# IndoorStation_PCB_M3.net
KiCad netlist of a schematic drawn in EAGLE
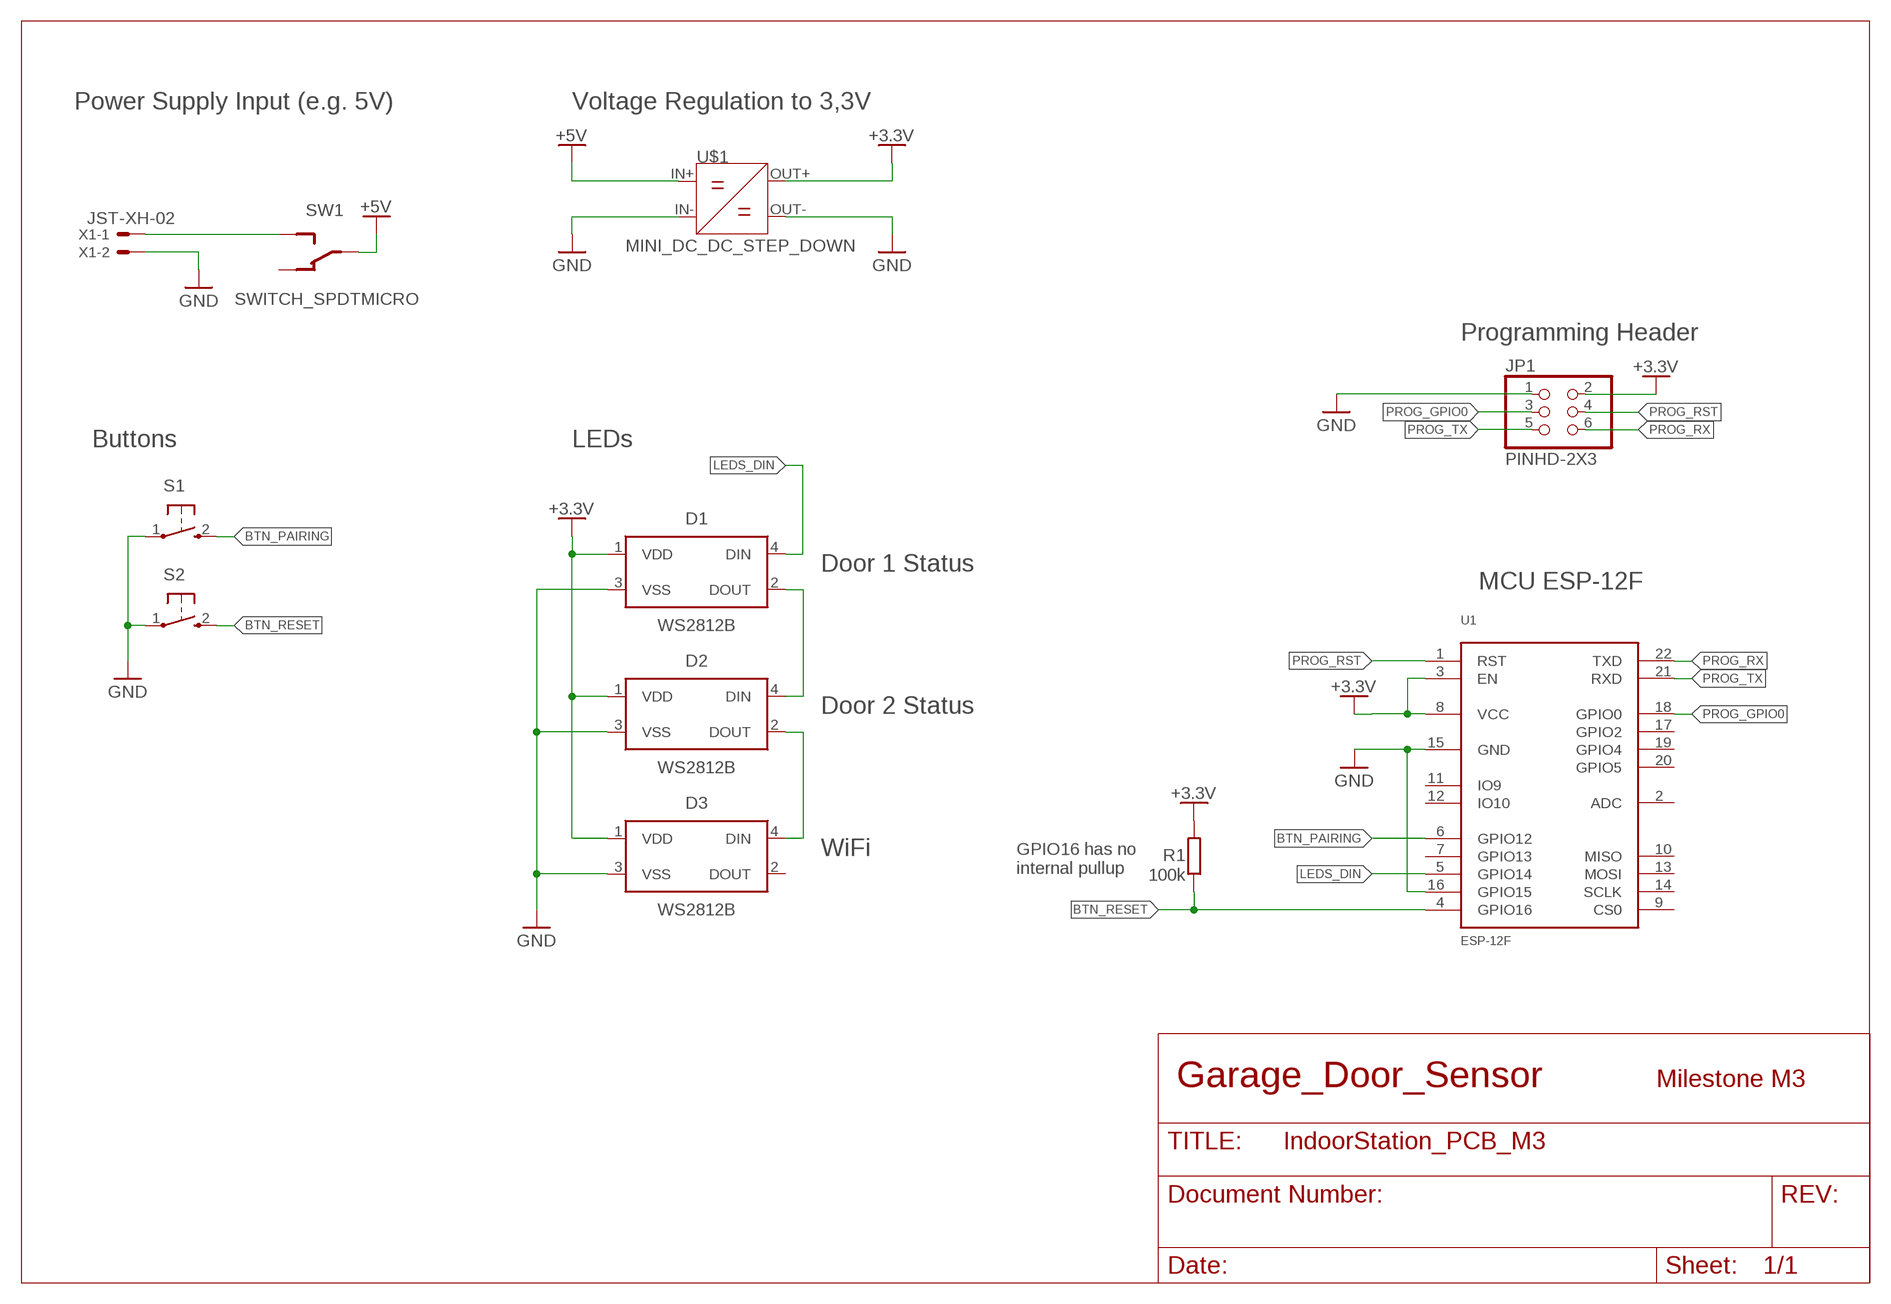
[diagram p0: schematic, sheet 1]

(export (version "E")
  (design (tool "Eeschema 10.0.6"))
  (components
    (comp (ref "D1")
      (value "WS2812B")
      (footprint "eagle-import:WS2812B")
      (fields (field (name "MANUFACTURER") "Worldsemi"))
      (libsource (lib "eagle-import") (part "WS2812B"))
    )
    (comp (ref "D2")
      (value "WS2812B")
      (footprint "eagle-import:WS2812B")
      (fields (field (name "MANUFACTURER") "Worldsemi"))
      (libsource (lib "eagle-import") (part "WS2812B"))
    )
    (comp (ref "D3")
      (value "WS2812B")
      (footprint "eagle-import:WS2812B")
      (fields (field (name "MANUFACTURER") "Worldsemi"))
      (libsource (lib "eagle-import") (part "WS2812B"))
    )
    (comp (ref "JP1")
      (value "PINHD-2X3")
      (footprint "eagle-import:2X03")
      (fields (field (name "MANUFACTURER") "Generic"))
      (libsource (lib "eagle-import") (part "PINHD-2X3"))
    )
    (comp (ref "R1")
      (value "100k")
      (footprint "eagle-import:R0805")
      (libsource (lib "eagle-import") (part "R-EU_R0805"))
    )
    (comp (ref "S1")
      (value "KURZHUBTASTER")
      (footprint "eagle-import:B3F-10XX")
      (libsource (lib "eagle-import") (part "KURZHUBTASTER"))
    )
    (comp (ref "S2")
      (value "KURZHUBTASTER")
      (footprint "eagle-import:B3F-10XX")
      (libsource (lib "eagle-import") (part "KURZHUBTASTER"))
    )
    (comp (ref "SW1")
      (value "SWITCH_SPDTMICRO")
      (footprint "eagle-import:MICROSWITCH_SPDT")
      (libsource (lib "eagle-import") (part "SWITCH_SPDTMICRO"))
    )
    (comp (ref "U$1")
      (value "MINI_DC_DC_STEP_DOWN")
      (footprint "eagle-import:MINI_DC_DC_STEP_DOWN")
      (libsource (lib "eagle-import") (part "MINI_DC_DC_STEP_DOWN"))
    )
    (comp (ref "U1")
      (value "ESP-12F")
      (footprint "eagle-import:ESP-12F")
      (fields (field (name "MF") "AI-Thinker"))
      (libsource (lib "eagle-import") (part "ESP-12F"))
    )
    (comp (ref "X1")
      (value "JST-XH-02")
      (footprint "eagle-import:JST-XH-02-EDGE")
      (libsource (lib "eagle-import") (part "JST-XH-02-PIN-EDGE"))
    )
  )
  (nets
    (net (code "1") (name "+3.3V") (class "Default")
      (node (ref "D1") (pin "1") (pinfunction "VDD_1") (pintype "power_in"))
      (node (ref "D2") (pin "1") (pinfunction "VDD_1") (pintype "power_in"))
      (node (ref "D3") (pin "1") (pinfunction "VDD_1") (pintype "power_in"))
      (node (ref "JP1") (pin "2") (pinfunction "2_2") (pintype "passive"))
      (node (ref "R1") (pin "2") (pinfunction "2_2") (pintype "passive"))
      (node (ref "U$1") (pin "OUT+") (pinfunction "OUT+_OUT+") (pintype "output"))
      (node (ref "U1") (pin "3") (pinfunction "EN_3") (pintype "bidirectional"))
      (node (ref "U1") (pin "8") (pinfunction "VCC_8") (pintype "bidirectional"))
    )
    (net (code "2") (name "+5V") (class "Default")
      (node (ref "SW1") (pin "P$2") (pinfunction "P$2_P$2") (pintype "passive"))
      (node (ref "U$1") (pin "IN+") (pinfunction "IN+_IN+") (pintype "input"))
    )
    (net (code "3") (name "BTN_PAIRING") (class "Default")
      (node (ref "S1") (pin "2") (pinfunction "S_2") (pintype "passive"))
      (node (ref "U1") (pin "6") (pinfunction "GPIO12_6") (pintype "bidirectional"))
    )
    (net (code "4") (name "BTN_RESET") (class "Default")
      (node (ref "R1") (pin "1") (pinfunction "1_1") (pintype "passive"))
      (node (ref "S2") (pin "2") (pinfunction "S_2") (pintype "passive"))
      (node (ref "U1") (pin "4") (pinfunction "GPIO16_4") (pintype "bidirectional"))
    )
    (net (code "5") (name "GND") (class "Default")
      (node (ref "D1") (pin "3") (pinfunction "VSS_3") (pintype "power_in"))
      (node (ref "D2") (pin "3") (pinfunction "VSS_3") (pintype "power_in"))
      (node (ref "D3") (pin "3") (pinfunction "VSS_3") (pintype "power_in"))
      (node (ref "JP1") (pin "1") (pinfunction "1_1") (pintype "passive"))
      (node (ref "S1") (pin "1") (pinfunction "P_1") (pintype "passive"))
      (node (ref "S2") (pin "1") (pinfunction "P_1") (pintype "passive"))
      (node (ref "U$1") (pin "IN-") (pinfunction "IN-_IN-") (pintype "input"))
      (node (ref "U$1") (pin "OUT-") (pinfunction "OUT-_OUT-") (pintype "output"))
      (node (ref "U1") (pin "15") (pinfunction "GND_15") (pintype "bidirectional"))
      (node (ref "U1") (pin "16") (pinfunction "GPIO15_16") (pintype "bidirectional"))
      (node (ref "X1") (pin "P$2") (pinfunction "S_P$2") (pintype "passive"))
    )
    (net (code "6") (name "LEDS_DIN") (class "Default")
      (node (ref "D1") (pin "4") (pinfunction "DIN_4") (pintype "input"))
      (node (ref "U1") (pin "5") (pinfunction "GPIO14_5") (pintype "bidirectional"))
    )
    (net (code "7") (name "Net-(D1-DOUT)") (class "Default")
      (node (ref "D1") (pin "2") (pinfunction "DOUT_2") (pintype "output"))
      (node (ref "D2") (pin "4") (pinfunction "DIN_4") (pintype "input"))
    )
    (net (code "8") (name "Net-(D2-DOUT)") (class "Default")
      (node (ref "D2") (pin "2") (pinfunction "DOUT_2") (pintype "output"))
      (node (ref "D3") (pin "4") (pinfunction "DIN_4") (pintype "input"))
    )
    (net (code "9") (name "Net-(X1A-S)") (class "Default")
      (node (ref "SW1") (pin "P$1") (pinfunction "P$1_P$1") (pintype "passive"))
      (node (ref "X1") (pin "P$1") (pinfunction "S_P$1") (pintype "passive"))
    )
    (net (code "10") (name "PROG_GPIO0") (class "Default")
      (node (ref "JP1") (pin "3") (pinfunction "3_3") (pintype "passive"))
      (node (ref "U1") (pin "18") (pinfunction "GPIO0_18") (pintype "bidirectional"))
    )
    (net (code "11") (name "PROG_RST") (class "Default")
      (node (ref "JP1") (pin "4") (pinfunction "4_4") (pintype "passive"))
      (node (ref "U1") (pin "1") (pinfunction "RST_1") (pintype "bidirectional"))
    )
    (net (code "12") (name "PROG_RX") (class "Default")
      (node (ref "JP1") (pin "6") (pinfunction "6_6") (pintype "passive"))
      (node (ref "U1") (pin "22") (pinfunction "TXD_22") (pintype "bidirectional"))
    )
    (net (code "13") (name "PROG_TX") (class "Default")
      (node (ref "JP1") (pin "5") (pinfunction "5_5") (pintype "passive"))
      (node (ref "U1") (pin "21") (pinfunction "RXD_21") (pintype "bidirectional"))
    )
    (net (code "14") (name "unconnected-(D3-DOUT-Pad2)") (class "Default")
      (node (ref "D3") (pin "2") (pinfunction "DOUT_2") (pintype "output"))
    )
    (net (code "15") (name "unconnected-(SW1-PadP$3)") (class "Default")
      (node (ref "SW1") (pin "P$3") (pinfunction "P$3_P$3") (pintype "passive"))
    )
    (net (code "16") (name "unconnected-(U1-ADC-Pad2)") (class "Default")
      (node (ref "U1") (pin "2") (pinfunction "ADC_2") (pintype "bidirectional"))
    )
    (net (code "17") (name "unconnected-(U1-CS0-Pad9)") (class "Default")
      (node (ref "U1") (pin "9") (pinfunction "CS0_9") (pintype "bidirectional"))
    )
    (net (code "18") (name "unconnected-(U1-GPIO2-Pad17)") (class "Default")
      (node (ref "U1") (pin "17") (pinfunction "GPIO2_17") (pintype "bidirectional"))
    )
    (net (code "19") (name "unconnected-(U1-GPIO4-Pad19)") (class "Default")
      (node (ref "U1") (pin "19") (pinfunction "GPIO4_19") (pintype "bidirectional"))
    )
    (net (code "20") (name "unconnected-(U1-GPIO5-Pad20)") (class "Default")
      (node (ref "U1") (pin "20") (pinfunction "GPIO5_20") (pintype "bidirectional"))
    )
    (net (code "21") (name "unconnected-(U1-GPIO13-Pad7)") (class "Default")
      (node (ref "U1") (pin "7") (pinfunction "GPIO13_7") (pintype "bidirectional"))
    )
    (net (code "22") (name "unconnected-(U1-IO9-Pad11)") (class "Default")
      (node (ref "U1") (pin "11") (pinfunction "IO9_11") (pintype "bidirectional"))
    )
    (net (code "23") (name "unconnected-(U1-IO10-Pad12)") (class "Default")
      (node (ref "U1") (pin "12") (pinfunction "IO10_12") (pintype "bidirectional"))
    )
    (net (code "24") (name "unconnected-(U1-MISO-Pad10)") (class "Default")
      (node (ref "U1") (pin "10") (pinfunction "MISO_10") (pintype "bidirectional"))
    )
    (net (code "25") (name "unconnected-(U1-MOSI-Pad13)") (class "Default")
      (node (ref "U1") (pin "13") (pinfunction "MOSI_13") (pintype "bidirectional"))
    )
    (net (code "26") (name "unconnected-(U1-SCLK-Pad14)") (class "Default")
      (node (ref "U1") (pin "14") (pinfunction "SCLK_14") (pintype "bidirectional"))
    )
  )
)
